# LineDriver.net
KiCad netlist of a schematic drawn in EAGLE
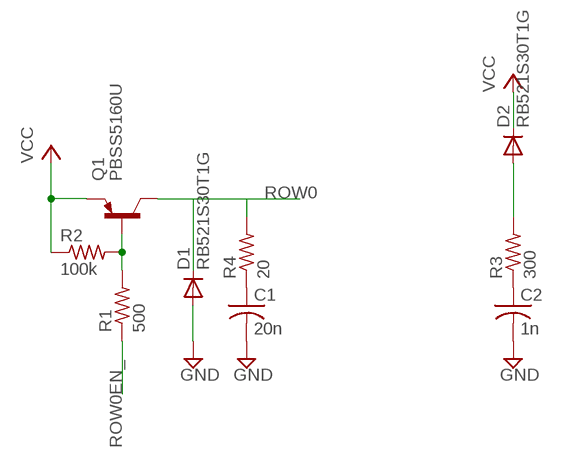
[diagram p0: schematic, sheet 1]

(export (version "E")
  (design (tool "Eeschema 10.0.6"))
  (components
    (comp (ref "C1")
      (value "20n")
      (footprint "eagle-import:C0805")
      (libsource (lib "eagle-import") (part "C-USC0805"))
    )
    (comp (ref "C2")
      (value "1n")
      (footprint "eagle-import:C0805")
      (libsource (lib "eagle-import") (part "C-USC0805"))
    )
    (comp (ref "D1")
      (value "RB521S30T1G")
      (footprint "eagle-import:SOD523")
      (libsource (lib "eagle-import") (part "DIODE-SOD523"))
    )
    (comp (ref "D2")
      (value "RB521S30T1G")
      (footprint "eagle-import:SOD523")
      (libsource (lib "eagle-import") (part "DIODE-SOD523"))
    )
    (comp (ref "Q1")
      (value "PBSS5160U")
      (footprint "eagle-import:SOT23-BCE")
      (libsource (lib "eagle-import") (part "-PNP-SOT23-BCE"))
    )
    (comp (ref "R1")
      (value "500")
      (footprint "eagle-import:R0805")
      (libsource (lib "eagle-import") (part "R-US_R0805"))
    )
    (comp (ref "R2")
      (value "100k")
      (footprint "eagle-import:R0805")
      (libsource (lib "eagle-import") (part "R-US_R0805"))
    )
    (comp (ref "R3")
      (value "300")
      (footprint "eagle-import:R0805")
      (libsource (lib "eagle-import") (part "R-US_R0805"))
    )
    (comp (ref "R4")
      (value "20")
      (footprint "eagle-import:R0805")
      (libsource (lib "eagle-import") (part "R-US_R0805"))
    )
  )
  (nets
    (net (code "1") (name "/ROW0") (class "Default")
      (node (ref "D1") (pin "C") (pinfunction "C_C") (pintype "passive"))
      (node (ref "Q1") (pin "C") (pinfunction "C_C") (pintype "passive"))
      (node (ref "R4") (pin "2") (pinfunction "2_2") (pintype "passive"))
    )
    (net (code "2") (name "/ROW0EN_") (class "Default")
      (node (ref "R1") (pin "1") (pinfunction "1_1") (pintype "passive"))
    )
    (net (code "3") (name "GND") (class "Default")
      (node (ref "C1") (pin "2") (pinfunction "2_2") (pintype "passive"))
      (node (ref "C2") (pin "2") (pinfunction "2_2") (pintype "passive"))
      (node (ref "D1") (pin "A") (pinfunction "A_A") (pintype "passive"))
    )
    (net (code "4") (name "Net-(C1-Pad1)") (class "Default")
      (node (ref "C1") (pin "1") (pinfunction "1_1") (pintype "passive"))
      (node (ref "R4") (pin "1") (pinfunction "1_1") (pintype "passive"))
    )
    (net (code "5") (name "Net-(C2-Pad1)") (class "Default")
      (node (ref "C2") (pin "1") (pinfunction "1_1") (pintype "passive"))
      (node (ref "R3") (pin "1") (pinfunction "1_1") (pintype "passive"))
    )
    (net (code "6") (name "Net-(D2-PadA)") (class "Default")
      (node (ref "D2") (pin "A") (pinfunction "A_A") (pintype "passive"))
      (node (ref "R3") (pin "2") (pinfunction "2_2") (pintype "passive"))
    )
    (net (code "7") (name "Net-(Q1-PadB)") (class "Default")
      (node (ref "Q1") (pin "B") (pinfunction "B_B") (pintype "passive"))
      (node (ref "R1") (pin "2") (pinfunction "2_2") (pintype "passive"))
      (node (ref "R2") (pin "2") (pinfunction "2_2") (pintype "passive"))
    )
    (net (code "8") (name "VCC") (class "Default")
      (node (ref "D2") (pin "C") (pinfunction "C_C") (pintype "passive"))
      (node (ref "Q1") (pin "E") (pinfunction "E_E") (pintype "passive"))
      (node (ref "R2") (pin "1") (pinfunction "1_1") (pintype "passive"))
    )
  )
)
